# 3_iip_quad_uart.net
KiCad netlist of a schematic drawn in Altium Designer
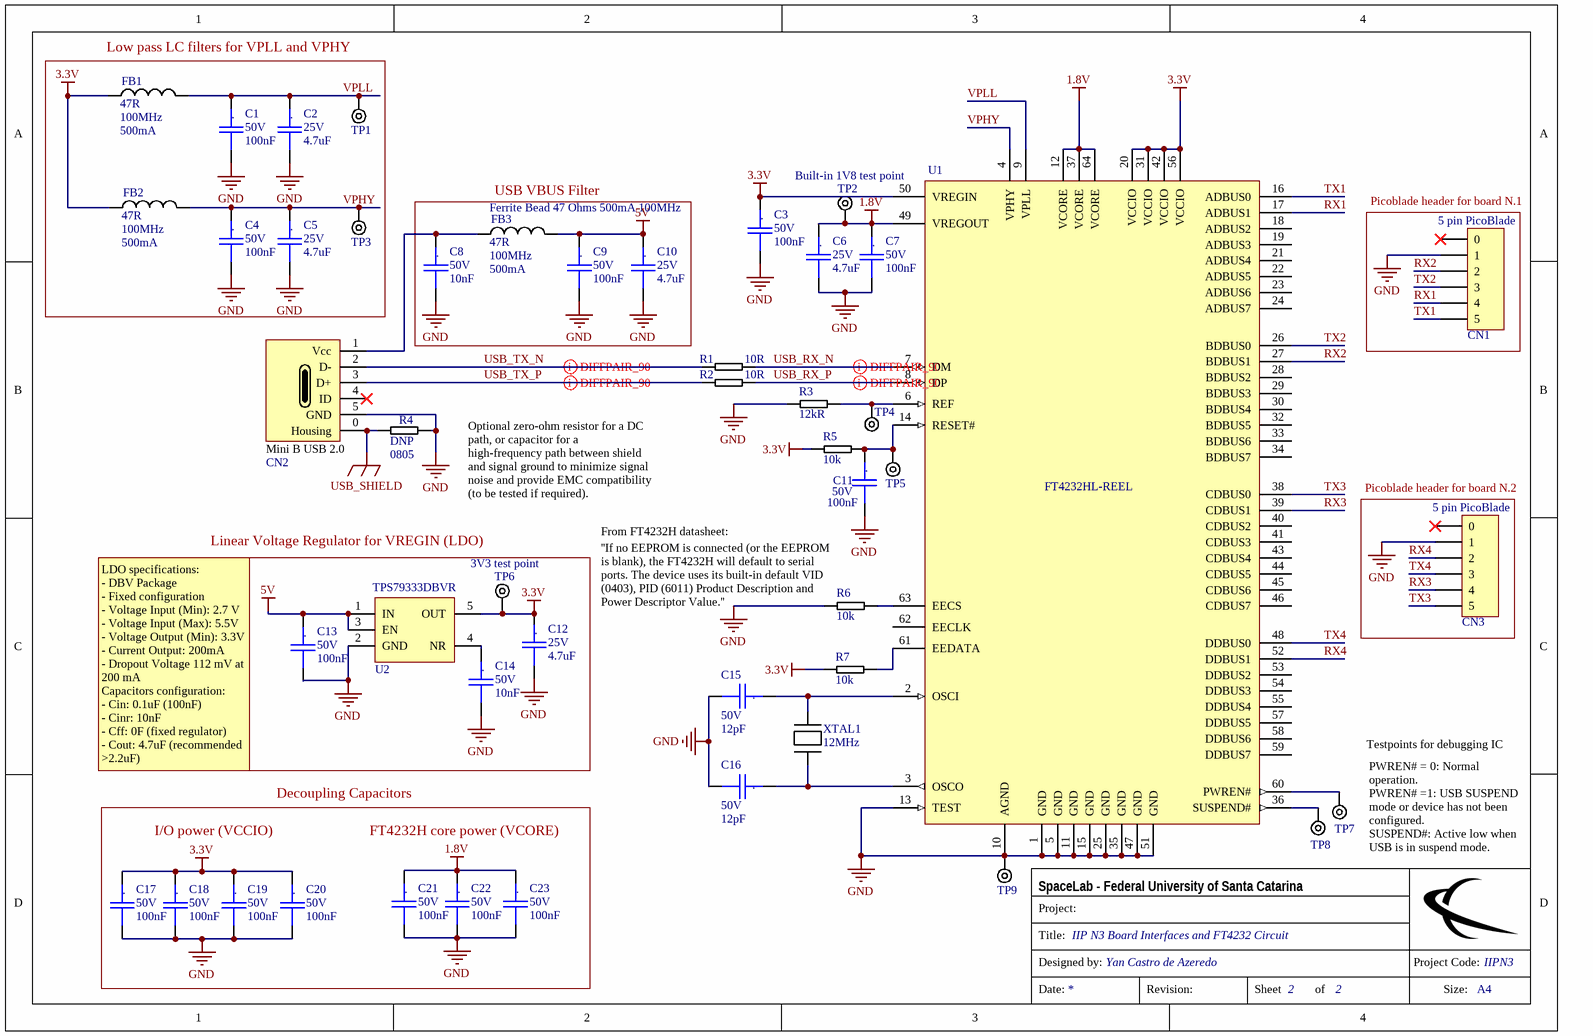
[diagram p0: 3_iip_quad_uart.SchDoc]

(export (version "E")
  (design (tool "Eeschema 10.0.6"))
  (components
    (comp (ref "C1")
      (value "0.1 uF, 0603 (1608 metric)")
      (footprint "C0603_MD")
      (fields
        (field (name "MANUFACTURER") "TDK")
        (field (name "TOLERANCE") "10%")
        (field (name "VOLTAGE") "50V")
        (field (name "VOLTAGE RATING") "50V")
        (field (name "CAPACITANCE") "100nF")
      )
      (libsource (lib "IB_floripasat2") (part "C1608X7R1H104K080AA"))
    )
    (comp (ref "C2")
      (value "4.7 uF, 0802 (2012 metric)")
      (footprint "C0805_MD")
      (description "Ceramic Capacitor SMD Multilayer, 0805 [2012 Metric], 4.7 uF, 25 V,  10%, X7R, C Series")
      (fields
        (field (name "MANUFACTURER") "TDK")
        (field (name "TOLERANCE") "10%")
        (field (name "VOLTAGE RATING") "25V")
        (field (name "CAPACITANCE") "4.7uF")
      )
      (libsource (lib "IB_floripasat2") (part "C2012X7R1E475K125AB"))
    )
    (comp (ref "C3")
      (value "0.1 uF, 0603 (1608 metric)")
      (footprint "C0603_MD")
      (fields
        (field (name "MANUFACTURER") "TDK")
        (field (name "TOLERANCE") "10%")
        (field (name "VOLTAGE") "50V")
        (field (name "VOLTAGE RATING") "50V")
        (field (name "CAPACITANCE") "100nF")
      )
      (libsource (lib "IB_floripasat2") (part "C1608X7R1H104K080AA"))
    )
    (comp (ref "C4")
      (value "0.1 uF, 0603 (1608 metric)")
      (footprint "C0603_MD")
      (fields
        (field (name "MANUFACTURER") "TDK")
        (field (name "TOLERANCE") "10%")
        (field (name "VOLTAGE") "50V")
        (field (name "VOLTAGE RATING") "50V")
        (field (name "CAPACITANCE") "100nF")
      )
      (libsource (lib "IB_floripasat2") (part "C1608X7R1H104K080AA"))
    )
    (comp (ref "C5")
      (value "4.7 uF, 0802 (2012 metric)")
      (footprint "C0805_MD")
      (description "Ceramic Capacitor SMD Multilayer, 0805 [2012 Metric], 4.7 uF, 25 V,  10%, X7R, C Series")
      (fields
        (field (name "MANUFACTURER") "TDK")
        (field (name "TOLERANCE") "10%")
        (field (name "VOLTAGE RATING") "25V")
        (field (name "CAPACITANCE") "4.7uF")
      )
      (libsource (lib "IB_floripasat2") (part "C2012X7R1E475K125AB"))
    )
    (comp (ref "C6")
      (value "4.7 uF, 0802 (2012 metric)")
      (footprint "C0805_MD")
      (description "Ceramic Capacitor SMD Multilayer, 0805 [2012 Metric], 4.7 uF, 25 V,  10%, X7R, C Series")
      (fields
        (field (name "MANUFACTURER") "TDK")
        (field (name "TOLERANCE") "10%")
        (field (name "VOLTAGE RATING") "25V")
        (field (name "CAPACITANCE") "4.7uF")
      )
      (libsource (lib "IB_floripasat2") (part "C2012X7R1E475K125AB"))
    )
    (comp (ref "C7")
      (value "0.1 uF, 0603 (1608 metric)")
      (footprint "C0603_MD")
      (fields
        (field (name "MANUFACTURER") "TDK")
        (field (name "TOLERANCE") "10%")
        (field (name "VOLTAGE") "50V")
        (field (name "VOLTAGE RATING") "50V")
        (field (name "CAPACITANCE") "100nF")
      )
      (libsource (lib "IB_floripasat2") (part "C1608X7R1H104K080AA"))
    )
    (comp (ref "C8")
      (value "10000 pF, 0805 (2012 metric)")
      (footprint "C0805_MD")
      (fields
        (field (name "MANUFACTURER") "Kyocera AVX")
        (field (name "TOLERANCE") "10%")
        (field (name "MANUFACTURER PART NUMBER") "08055C103KAT4A")
        (field (name "VOLTAGE") "50V")
        (field (name "CAPACITANCE") "10nF")
      )
      (libsource (lib "IB_floripasat2") (part "08055C103KAT4A"))
    )
    (comp (ref "C9")
      (value "0.1 uF, 0603 (1608 metric)")
      (footprint "C0603_MD")
      (fields
        (field (name "MANUFACTURER") "TDK")
        (field (name "TOLERANCE") "10%")
        (field (name "VOLTAGE") "50V")
        (field (name "VOLTAGE RATING") "50V")
        (field (name "CAPACITANCE") "100nF")
      )
      (libsource (lib "IB_floripasat2") (part "C1608X7R1H104K080AA"))
    )
    (comp (ref "C10")
      (value "4.7 uF, 0802 (2012 metric)")
      (footprint "C0805_MD")
      (description "Ceramic Capacitor SMD Multilayer, 0805 [2012 Metric], 4.7 uF, 25 V,  10%, X7R, C Series")
      (fields
        (field (name "MANUFACTURER") "TDK")
        (field (name "TOLERANCE") "10%")
        (field (name "VOLTAGE RATING") "25V")
        (field (name "CAPACITANCE") "4.7uF")
      )
      (libsource (lib "IB_floripasat2") (part "C2012X7R1E475K125AB"))
    )
    (comp (ref "C11")
      (value "0.1 uF, 0603 (1608 metric)")
      (footprint "C0603_MD")
      (fields
        (field (name "MANUFACTURER") "TDK")
        (field (name "TOLERANCE") "10%")
        (field (name "VOLTAGE") "50V")
        (field (name "VOLTAGE RATING") "50V")
        (field (name "CAPACITANCE") "100nF")
      )
      (libsource (lib "IB_floripasat2") (part "C1608X7R1H104K080AA"))
    )
    (comp (ref "C12")
      (value "4.7 uF, 0802 (2012 metric)")
      (footprint "C0805_MD")
      (description "Ceramic Capacitor SMD Multilayer, 0805 [2012 Metric], 4.7 uF, 25 V,  10%, X7R, C Series")
      (fields
        (field (name "MANUFACTURER") "TDK")
        (field (name "TOLERANCE") "10%")
        (field (name "VOLTAGE RATING") "25V")
        (field (name "CAPACITANCE") "4.7uF")
      )
      (libsource (lib "IB_floripasat2") (part "C2012X7R1E475K125AB"))
    )
    (comp (ref "C13")
      (value "0.1 uF, 0603 (1608 metric)")
      (footprint "C0603_MD")
      (fields
        (field (name "MANUFACTURER") "TDK")
        (field (name "TOLERANCE") "10%")
        (field (name "VOLTAGE") "50V")
        (field (name "VOLTAGE RATING") "50V")
        (field (name "CAPACITANCE") "100nF")
      )
      (libsource (lib "IB_floripasat2") (part "C1608X7R1H104K080AA"))
    )
    (comp (ref "C14")
      (value "10000 pF, 0805 (2012 metric)")
      (footprint "C0805_MD")
      (fields
        (field (name "MANUFACTURER") "Kyocera AVX")
        (field (name "TOLERANCE") "10%")
        (field (name "MANUFACTURER PART NUMBER") "08055C103KAT4A")
        (field (name "VOLTAGE") "50V")
        (field (name "CAPACITANCE") "10nF")
      )
      (libsource (lib "IB_floripasat2") (part "08055C103KAT4A"))
    )
    (comp (ref "C15")
      (value "12 pF, 0603 (1608 metric)")
      (footprint "C0603_MD")
      (description "Cap Ceramic 12pF 50VDC C0G 5% SMD 0603 Paper T/R")
      (fields
        (field (name "MANUFACTURER") "Samsung")
        (field (name "MANUFACTURER PART NUMBER") "CL10C120JB8NNNC")
        (field (name "VOLTAGE") "50V")
        (field (name "CAPACITANCE") "12pF")
      )
      (libsource (lib "IB_floripasat2") (part "CL10C120JB8NNNC"))
    )
    (comp (ref "C16")
      (value "12 pF, 0603 (1608 metric)")
      (footprint "C0603_MD")
      (description "Cap Ceramic 12pF 50VDC C0G 5% SMD 0603 Paper T/R")
      (fields
        (field (name "MANUFACTURER") "Samsung")
        (field (name "MANUFACTURER PART NUMBER") "CL10C120JB8NNNC")
        (field (name "VOLTAGE") "50V")
        (field (name "CAPACITANCE") "12pF")
      )
      (libsource (lib "IB_floripasat2") (part "CL10C120JB8NNNC"))
    )
    (comp (ref "C17")
      (value "0.1 uF, 0603 (1608 metric)")
      (footprint "C0603_MD")
      (fields
        (field (name "MANUFACTURER") "TDK")
        (field (name "TOLERANCE") "10%")
        (field (name "VOLTAGE") "50V")
        (field (name "VOLTAGE RATING") "50V")
        (field (name "CAPACITANCE") "100nF")
      )
      (libsource (lib "IB_floripasat2") (part "C1608X7R1H104K080AA"))
    )
    (comp (ref "C18")
      (value "0.1 uF, 0603 (1608 metric)")
      (footprint "C0603_MD")
      (fields
        (field (name "MANUFACTURER") "TDK")
        (field (name "TOLERANCE") "10%")
        (field (name "VOLTAGE") "50V")
        (field (name "VOLTAGE RATING") "50V")
        (field (name "CAPACITANCE") "100nF")
      )
      (libsource (lib "IB_floripasat2") (part "C1608X7R1H104K080AA"))
    )
    (comp (ref "C19")
      (value "0.1 uF, 0603 (1608 metric)")
      (footprint "C0603_MD")
      (fields
        (field (name "MANUFACTURER") "TDK")
        (field (name "TOLERANCE") "10%")
        (field (name "VOLTAGE") "50V")
        (field (name "VOLTAGE RATING") "50V")
        (field (name "CAPACITANCE") "100nF")
      )
      (libsource (lib "IB_floripasat2") (part "C1608X7R1H104K080AA"))
    )
    (comp (ref "C20")
      (value "0.1 uF, 0603 (1608 metric)")
      (footprint "C0603_MD")
      (fields
        (field (name "MANUFACTURER") "TDK")
        (field (name "TOLERANCE") "10%")
        (field (name "VOLTAGE") "50V")
        (field (name "VOLTAGE RATING") "50V")
        (field (name "CAPACITANCE") "100nF")
      )
      (libsource (lib "IB_floripasat2") (part "C1608X7R1H104K080AA"))
    )
    (comp (ref "C21")
      (value "0.1 uF, 0603 (1608 metric)")
      (footprint "C0603_MD")
      (fields
        (field (name "MANUFACTURER") "TDK")
        (field (name "TOLERANCE") "10%")
        (field (name "VOLTAGE") "50V")
        (field (name "VOLTAGE RATING") "50V")
        (field (name "CAPACITANCE") "100nF")
      )
      (libsource (lib "IB_floripasat2") (part "C1608X7R1H104K080AA"))
    )
    (comp (ref "C22")
      (value "0.1 uF, 0603 (1608 metric)")
      (footprint "C0603_MD")
      (fields
        (field (name "MANUFACTURER") "TDK")
        (field (name "TOLERANCE") "10%")
        (field (name "VOLTAGE") "50V")
        (field (name "VOLTAGE RATING") "50V")
        (field (name "CAPACITANCE") "100nF")
      )
      (libsource (lib "IB_floripasat2") (part "C1608X7R1H104K080AA"))
    )
    (comp (ref "C23")
      (value "0.1 uF, 0603 (1608 metric)")
      (footprint "C0603_MD")
      (fields
        (field (name "MANUFACTURER") "TDK")
        (field (name "TOLERANCE") "10%")
        (field (name "VOLTAGE") "50V")
        (field (name "VOLTAGE RATING") "50V")
        (field (name "CAPACITANCE") "100nF")
      )
      (libsource (lib "IB_floripasat2") (part "C1608X7R1H104K080AA"))
    )
    (comp (ref "CN1")
      (value "5 pin PicoBlade")
      (footprint "PICO BLADE 0533980571")
      (description "Wire-To-Board Connector, Vertical, PicoBlade 53398 Series, Surface Mount, Header, 5, 1.25 mm")
      (fields (field (name "MANUFACTURER") "Molex") (field (name "MANUFACTURER PART NUMBER") "53398-0571"))
      (libsource (lib "IB_floripasat2") (part "53398-0571"))
    )
    (comp (ref "CN2")
      (value "Vertical mini B USB 2.0 port")
      (footprint "MINI USB B 180GRAUS WE")
      (fields
        (field (name "MANUFACTURER") "Wurth Electronics")
        (field (name "MANUFACTURER PART NUMBER") "651005136421")
      )
      (libsource (lib "IB_floripasat2") (part "651005136421"))
    )
    (comp (ref "CN3")
      (value "5 pin PicoBlade")
      (footprint "PICO BLADE 0533980571")
      (description "Wire-To-Board Connector, Vertical, PicoBlade 53398 Series, Surface Mount, Header, 5, 1.25 mm")
      (fields (field (name "MANUFACTURER") "Molex") (field (name "MANUFACTURER PART NUMBER") "53398-0571"))
      (libsource (lib "IB_floripasat2") (part "53398-0571"))
    )
    (comp (ref "FB1")
      (value "Ferrite Bead 47 Ohms 500mA 100MHz")
      (footprint "L0603")
      (description "WURTH ELEKTRONIK   742792608   FERRITE BEAD, 0.1 OHM, 0.5A, 0603")
      (fields
        (field (name "MANUFACTURER") "Wurth Electronics")
        (field (name "TOLERANCE") "25%")
        (field (name "IMPEDANCE") "47R")
        (field (name "TEST FREQUENCY") "100MHz")
        (field (name "CURRENT RATING") "500mA")
      )
      (libsource (lib "IB_floripasat2") (part "742792608"))
    )
    (comp (ref "FB2")
      (value "Ferrite Bead 47 Ohms 500mA 100MHz")
      (footprint "L0603")
      (description "WURTH ELEKTRONIK   742792608   FERRITE BEAD, 0.1 OHM, 0.5A, 0603")
      (fields
        (field (name "MANUFACTURER") "Wurth Electronics")
        (field (name "TOLERANCE") "25%")
        (field (name "IMPEDANCE") "47R")
        (field (name "TEST FREQUENCY") "100MHz")
        (field (name "CURRENT RATING") "500mA")
      )
      (libsource (lib "IB_floripasat2") (part "742792608"))
    )
    (comp (ref "FB3")
      (value "Ferrite Bead 47 Ohms 500mA 100MHz")
      (footprint "L0603")
      (description "WURTH ELEKTRONIK   742792608   FERRITE BEAD, 0.1 OHM, 0.5A, 0603")
      (fields
        (field (name "MANUFACTURER") "Wurth Electronics")
        (field (name "TOLERANCE") "25%")
        (field (name "IMPEDANCE") "47R")
        (field (name "TEST FREQUENCY") "100MHz")
        (field (name "CURRENT RATING") "500mA")
      )
      (libsource (lib "IB_floripasat2") (part "742792608"))
    )
    (comp (ref "R1")
      (value "RES 10 ohms (0603)")
      (footprint "R0603_MD")
      (description "YAGEO (PHYCOMP) - RC0603FR-0710RL - RES, THICK FILM, 10R, 1%, 0.1W, 0603")
      (fields
        (field (name "MANUFACTURER") "Yageo")
        (field (name "TOLERANCE") "1%")
        (field (name "RESISTANCE") "10R")
      )
      (libsource (lib "IB_floripasat2") (part "RC0603FR-0710RL"))
    )
    (comp (ref "R2")
      (value "RES 10 ohms (0603)")
      (footprint "R0603_MD")
      (description "YAGEO (PHYCOMP) - RC0603FR-0710RL - RES, THICK FILM, 10R, 1%, 0.1W, 0603")
      (fields
        (field (name "MANUFACTURER") "Yageo")
        (field (name "TOLERANCE") "1%")
        (field (name "RESISTANCE") "10R")
      )
      (libsource (lib "IB_floripasat2") (part "RC0603FR-0710RL"))
    )
    (comp (ref "R3")
      (value "RES 12K ohms (0805)")
      (footprint "R0805_MD")
      (description "Resistor, SMT, 0805, 12K Ohm, +/-1%, +/-100ppm, Thk Film, T/R Marked")
      (fields
        (field (name "MANUFACTURER") "Stackpole Electronics")
        (field (name "MANUFACTURER PART NUMBER") "RMCF0805FT12K0")
        (field (name "RESISTANCE") "12kR")
      )
      (libsource (lib "IB_floripasat2") (part "RMCF0805FT12K0"))
    )
    (comp (ref "R4")
      (value "DNP")
      (footprint "R0805_MD")
      (fields
        (field (name "MANUFACTURER") "Vishay")
        (field (name "TOLERANCE") "1%")
        (field (name "MANUFACTURER PART NUMBER") "CRCW08050000Z0EA")
        (field (name "CASE/PACKAGE") "0805")
      )
      (libsource (lib "IB_floripasat2") (part "CRCW08050000Z0EA"))
    )
    (comp (ref "R5")
      (value "10k")
      (footprint "R0805_MD")
      (description "RES 10.0K OHM 1/8W 1% 0805 SMD")
      (fields (field (name "MANUFACTURER") "Vishay Dale") (field (name "TOLERANCE") "1%"))
      (libsource (lib "IB_floripasat2") (part "CRCW080510K0FKEA"))
    )
    (comp (ref "R6")
      (value "10k")
      (footprint "R0805_MD")
      (description "RES 10.0K OHM 1/8W 1% 0805 SMD")
      (fields (field (name "MANUFACTURER") "Vishay Dale") (field (name "TOLERANCE") "1%"))
      (libsource (lib "IB_floripasat2") (part "CRCW080510K0FKEA"))
    )
    (comp (ref "R7")
      (value "10k")
      (footprint "R0805_MD")
      (description "RES 10.0K OHM 1/8W 1% 0805 SMD")
      (fields (field (name "MANUFACTURER") "Vishay Dale") (field (name "TOLERANCE") "1%"))
      (libsource (lib "IB_floripasat2") (part "CRCW080510K0FKEA"))
    )
    (comp (ref "TP1")
      (value "DNP")
      (footprint "TEST POINT PTH")
      (description "TEST POINT PAD")
      (libsource (lib "IB_floripasat2") (part "Test Point PTH"))
    )
    (comp (ref "TP2")
      (value "DNP")
      (footprint "TEST POINT PTH")
      (description "TEST POINT PAD")
      (libsource (lib "IB_floripasat2") (part "Test Point PTH"))
    )
    (comp (ref "TP3")
      (value "DNP")
      (footprint "TEST POINT PTH")
      (description "TEST POINT PAD")
      (libsource (lib "IB_floripasat2") (part "Test Point PTH"))
    )
    (comp (ref "TP4")
      (value "DNP")
      (footprint "TEST POINT PTH")
      (description "TEST POINT PAD")
      (libsource (lib "IB_floripasat2") (part "Test Point PTH"))
    )
    (comp (ref "TP5")
      (value "DNP")
      (footprint "TEST POINT PTH")
      (description "TEST POINT PAD")
      (libsource (lib "IB_floripasat2") (part "Test Point PTH"))
    )
    (comp (ref "TP6")
      (value "DNP")
      (footprint "TEST POINT PTH")
      (description "TEST POINT PAD")
      (libsource (lib "IB_floripasat2") (part "Test Point PTH"))
    )
    (comp (ref "TP7")
      (value "DNP")
      (footprint "TEST POINT PTH")
      (description "TEST POINT PAD")
      (libsource (lib "IB_floripasat2") (part "Test Point PTH"))
    )
    (comp (ref "TP8")
      (value "DNP")
      (footprint "TEST POINT PTH")
      (description "TEST POINT PAD")
      (libsource (lib "IB_floripasat2") (part "Test Point PTH"))
    )
    (comp (ref "TP9")
      (value "DNP")
      (footprint "TEST POINT PTH")
      (description "TEST POINT PAD")
      (libsource (lib "IB_floripasat2") (part "Test Point PTH"))
    )
    (comp (ref "U1")
      (value "FT4232HL-REEL")
      (footprint "LQFP-64")
      (description "FTDI - FT4232HL-REEL - USB-UART/MPSSE, 4232, QUAD, 64LQFP")
      (fields (field (name "MANUFACTURER") "FTDI"))
      (libsource (lib "IB_floripasat2") (part "FT4232HL-REEL"))
    )
    (comp (ref "U2")
      (value "TPS79333DBVR")
      (footprint "SOT23-5")
      (description "TEXAS INSTRUMENTS - TPS79333DBVR - IC, V REG, LINEAR, 0.2A, SOT-23-5")
      (fields (field (name "MANUFACTURER") "Texas Instruments"))
      (libsource (lib "IB_floripasat2") (part "TPS79333DBVR"))
    )
    (comp (ref "XTAL1")
      (value "12.000MHz 12pF")
      (footprint "TXC 7A Series")
      (description "Crystals 12.000MHz 30ppm 12pF -40C to 85C")
      (fields
        (field (name "MANUFACTURER") "TXC")
        (field (name "TOLERANCE") "30ppm")
        (field (name "FREQUENCY") "12MHz")
      )
      (libsource (lib "IB_floripasat2") (part "AA-12.000MAGE-T"))
    )
  )
  (nets
    (net (code "1") (name "/RX1") (class "Default")
      (node (ref "CN1") (pin "4") (pinfunction "4_4") (pintype "passive"))
      (node (ref "U1") (pin "17") (pinfunction "ADBUS1_17") (pintype "passive"))
    )
    (net (code "2") (name "/RX2") (class "Default")
      (node (ref "CN1") (pin "2") (pinfunction "2_2") (pintype "passive"))
      (node (ref "U1") (pin "27") (pinfunction "BDBUS1_27") (pintype "passive"))
    )
    (net (code "3") (name "/RX3") (class "Default")
      (node (ref "CN3") (pin "4") (pinfunction "4_4") (pintype "passive"))
      (node (ref "U1") (pin "39") (pinfunction "CDBUS1_39") (pintype "passive"))
    )
    (net (code "4") (name "/RX4") (class "Default")
      (node (ref "CN3") (pin "2") (pinfunction "2_2") (pintype "passive"))
      (node (ref "U1") (pin "52") (pinfunction "DDBUS1_52") (pintype "passive"))
    )
    (net (code "5") (name "/TX1") (class "Default")
      (node (ref "CN1") (pin "5") (pinfunction "5_5") (pintype "passive"))
      (node (ref "U1") (pin "16") (pinfunction "ADBUS0_16") (pintype "passive"))
    )
    (net (code "6") (name "/TX2") (class "Default")
      (node (ref "CN1") (pin "3") (pinfunction "3_3") (pintype "passive"))
      (node (ref "U1") (pin "26") (pinfunction "BDBUS0_26") (pintype "passive"))
    )
    (net (code "7") (name "/TX3") (class "Default")
      (node (ref "CN3") (pin "5") (pinfunction "5_5") (pintype "passive"))
      (node (ref "U1") (pin "38") (pinfunction "CDBUS0_38") (pintype "passive"))
    )
    (net (code "8") (name "/TX4") (class "Default")
      (node (ref "CN3") (pin "3") (pinfunction "3_3") (pintype "passive"))
      (node (ref "U1") (pin "48") (pinfunction "DDBUS0_48") (pintype "passive"))
    )
    (net (code "9") (name "/USB_RX_N") (class "Default")
      (node (ref "R1") (pin "2") (pinfunction "2_2") (pintype "passive"))
      (node (ref "U1") (pin "7") (pinfunction "DM_7") (pintype "bidirectional"))
    )
    (net (code "10") (name "/USB_RX_P") (class "Default")
      (node (ref "R2") (pin "2") (pinfunction "2_2") (pintype "passive"))
      (node (ref "U1") (pin "8") (pinfunction "DP_8") (pintype "bidirectional"))
    )
    (net (code "11") (name "/USB_TX_N") (class "Default")
      (node (ref "CN2") (pin "2") (pinfunction "D-_2") (pintype "passive"))
      (node (ref "R1") (pin "1") (pinfunction "1_1") (pintype "passive"))
    )
    (net (code "12") (name "/USB_TX_P") (class "Default")
      (node (ref "CN2") (pin "3") (pinfunction "D+_3") (pintype "passive"))
      (node (ref "R2") (pin "1") (pinfunction "1_1") (pintype "passive"))
    )
    (net (code "13") (name "/VPHY") (class "Default")
      (node (ref "C4") (pin "1") (pinfunction "1_1") (pintype "passive"))
      (node (ref "C5") (pin "1") (pinfunction "1_1") (pintype "passive"))
      (node (ref "FB2") (pin "2") (pinfunction "2_2") (pintype "passive"))
      (node (ref "TP3") (pin "1") (pinfunction "1_1") (pintype "passive"))
      (node (ref "U1") (pin "4") (pinfunction "VPHY_4") (pintype "power_in"))
    )
    (net (code "14") (name "/VPLL") (class "Default")
      (node (ref "C1") (pin "1") (pinfunction "1_1") (pintype "passive"))
      (node (ref "C2") (pin "1") (pinfunction "1_1") (pintype "passive"))
      (node (ref "FB1") (pin "2") (pinfunction "2_2") (pintype "passive"))
      (node (ref "TP1") (pin "1") (pinfunction "1_1") (pintype "passive"))
      (node (ref "U1") (pin "9") (pinfunction "VPLL_9") (pintype "power_in"))
    )
    (net (code "15") (name "1.8V") (class "Default")
      (node (ref "C21") (pin "1") (pinfunction "1_1") (pintype "passive"))
      (node (ref "C22") (pin "1") (pinfunction "1_1") (pintype "passive"))
      (node (ref "C23") (pin "1") (pinfunction "1_1") (pintype "passive"))
      (node (ref "C6") (pin "1") (pinfunction "1_1") (pintype "passive"))
      (node (ref "C7") (pin "1") (pinfunction "1_1") (pintype "passive"))
      (node (ref "TP2") (pin "1") (pinfunction "1_1") (pintype "passive"))
      (node (ref "U1") (pin "12") (pinfunction "VCORE_12") (pintype "power_in"))
      (node (ref "U1") (pin "37") (pinfunction "VCORE_37") (pintype "power_in"))
      (node (ref "U1") (pin "49") (pinfunction "VREGOUT_49") (pintype "passive"))
      (node (ref "U1") (pin "64") (pinfunction "VCORE_64") (pintype "power_in"))
    )
    (net (code "16") (name "3.3V") (class "Default")
      (node (ref "C12") (pin "1") (pinfunction "1_1") (pintype "passive"))
      (node (ref "C17") (pin "1") (pinfunction "1_1") (pintype "passive"))
      (node (ref "C18") (pin "1") (pinfunction "1_1") (pintype "passive"))
      (node (ref "C19") (pin "1") (pinfunction "1_1") (pintype "passive"))
      (node (ref "C20") (pin "1") (pinfunction "1_1") (pintype "passive"))
      (node (ref "C3") (pin "1") (pinfunction "1_1") (pintype "passive"))
      (node (ref "FB1") (pin "1") (pinfunction "1_1") (pintype "passive"))
      (node (ref "FB2") (pin "1") (pinfunction "1_1") (pintype "passive"))
      (node (ref "R5") (pin "1") (pinfunction "1_1") (pintype "passive"))
      (node (ref "R7") (pin "1") (pinfunction "1_1") (pintype "passive"))
      (node (ref "TP6") (pin "1") (pinfunction "1_1") (pintype "passive"))
      (node (ref "U1") (pin "20") (pinfunction "VCCIO_20") (pintype "power_in"))
      (node (ref "U1") (pin "31") (pinfunction "VCCIO_31") (pintype "power_in"))
      (node (ref "U1") (pin "42") (pinfunction "VCCIO_42") (pintype "power_in"))
      (node (ref "U1") (pin "50") (pinfunction "VREGIN_50") (pintype "passive"))
      (node (ref "U1") (pin "56") (pinfunction "VCCIO_56") (pintype "power_in"))
      (node (ref "U2") (pin "5") (pinfunction "OUT_5") (pintype "passive"))
    )
    (net (code "17") (name "5V") (class "Default")
      (node (ref "C10") (pin "1") (pinfunction "1_1") (pintype "passive"))
      (node (ref "C13") (pin "1") (pinfunction "1_1") (pintype "passive"))
      (node (ref "C9") (pin "1") (pinfunction "1_1") (pintype "passive"))
      (node (ref "FB3") (pin "2") (pinfunction "2_2") (pintype "passive"))
      (node (ref "U2") (pin "1") (pinfunction "IN_1") (pintype "passive"))
      (node (ref "U2") (pin "3") (pinfunction "EN_3") (pintype "passive"))
    )
    (net (code "18") (name "GND") (class "Default")
      (node (ref "C1") (pin "2") (pinfunction "2_2") (pintype "passive"))
      (node (ref "C10") (pin "2") (pinfunction "2_2") (pintype "passive"))
      (node (ref "C11") (pin "2") (pinfunction "2_2") (pintype "passive"))
      (node (ref "C12") (pin "2") (pinfunction "2_2") (pintype "passive"))
      (node (ref "C13") (pin "2") (pinfunction "2_2") (pintype "passive"))
      (node (ref "C14") (pin "2") (pinfunction "2_2") (pintype "passive"))
      (node (ref "C15") (pin "2") (pinfunction "2_2") (pintype "passive"))
      (node (ref "C16") (pin "2") (pinfunction "2_2") (pintype "passive"))
      (node (ref "C17") (pin "2") (pinfunction "2_2") (pintype "passive"))
      (node (ref "C18") (pin "2") (pinfunction "2_2") (pintype "passive"))
      (node (ref "C19") (pin "2") (pinfunction "2_2") (pintype "passive"))
      (node (ref "C2") (pin "2") (pinfunction "2_2") (pintype "passive"))
      (node (ref "C20") (pin "2") (pinfunction "2_2") (pintype "passive"))
      (node (ref "C21") (pin "2") (pinfunction "2_2") (pintype "passive"))
      (node (ref "C22") (pin "2") (pinfunction "2_2") (pintype "passive"))
      (node (ref "C23") (pin "2") (pinfunction "2_2") (pintype "passive"))
      (node (ref "C3") (pin "2") (pinfunction "2_2") (pintype "passive"))
      (node (ref "C4") (pin "2") (pinfunction "2_2") (pintype "passive"))
      (node (ref "C5") (pin "2") (pinfunction "2_2") (pintype "passive"))
      (node (ref "C6") (pin "2") (pinfunction "2_2") (pintype "passive"))
      (node (ref "C7") (pin "2") (pinfunction "2_2") (pintype "passive"))
      (node (ref "C8") (pin "2") (pinfunction "2_2") (pintype "passive"))
      (node (ref "C9") (pin "2") (pinfunction "2_2") (pintype "passive"))
      (node (ref "CN1") (pin "1") (pinfunction "1_1") (pintype "passive"))
      (node (ref "CN2") (pin "5") (pinfunction "GND_5") (pintype "passive"))
      (node (ref "CN3") (pin "1") (pinfunction "1_1") (pintype "passive"))
      (node (ref "R3") (pin "1") (pinfunction "1_1") (pintype "passive"))
      (node (ref "R4") (pin "2") (pinfunction "2_2") (pintype "passive"))
      (node (ref "R6") (pin "1") (pinfunction "1_1") (pintype "passive"))
      (node (ref "TP9") (pin "1") (pinfunction "1_1") (pintype "passive"))
      (node (ref "U1") (pin "1") (pinfunction "GND_1") (pintype "passive"))
      (node (ref "U1") (pin "10") (pinfunction "AGND_10") (pintype "passive"))
      (node (ref "U1") (pin "11") (pinfunction "GND_11") (pintype "passive"))
      (node (ref "U1") (pin "13") (pinfunction "TEST_13") (pintype "input"))
      (node (ref "U1") (pin "15") (pinfunction "GND_15") (pintype "passive"))
      (node (ref "U1") (pin "25") (pinfunction "GND_25") (pintype "passive"))
      (node (ref "U1") (pin "35") (pinfunction "GND_35") (pintype "passive"))
      (node (ref "U1") (pin "47") (pinfunction "GND_47") (pintype "passive"))
      (node (ref "U1") (pin "5") (pinfunction "GND_5") (pintype "passive"))
      (node (ref "U1") (pin "51") (pinfunction "GND_51") (pintype "passive"))
      (node (ref "U2") (pin "2") (pinfunction "GND_2") (pintype "passive"))
    )
    (net (code "19") (name "Net-(CN2-Vcc)") (class "Default")
      (node (ref "C8") (pin "1") (pinfunction "1_1") (pintype "passive"))
      (node (ref "CN2") (pin "1") (pinfunction "Vcc_1") (pintype "passive"))
      (node (ref "FB3") (pin "1") (pinfunction "1_1") (pintype "passive"))
    )
    (net (code "20") (name "Net-(U1-EECS)") (class "Default")
      (node (ref "R6") (pin "2") (pinfunction "2_2") (pintype "passive"))
      (node (ref "U1") (pin "63") (pinfunction "EECS_63") (pintype "passive"))
    )
    (net (code "21") (name "Net-(U1-EEDATA)") (class "Default")
      (node (ref "R7") (pin "2") (pinfunction "2_2") (pintype "passive"))
      (node (ref "U1") (pin "61") (pinfunction "EEDATA_61") (pintype "passive"))
    )
    (net (code "22") (name "Net-(U1-OSCI)") (class "Default")
      (node (ref "C15") (pin "1") (pinfunction "1_1") (pintype "passive"))
      (node (ref "U1") (pin "2") (pinfunction "OSCI_2") (pintype "input"))
      (node (ref "XTAL1") (pin "1") (pinfunction "1_1") (pintype "passive"))
    )
    (net (code "23") (name "Net-(U1-OSCO)") (class "Default")
      (node (ref "C16") (pin "1") (pinfunction "1_1") (pintype "passive"))
      (node (ref "U1") (pin "3") (pinfunction "OSCO_3") (pintype "output"))
      (node (ref "XTAL1") (pin "2") (pinfunction "2_2") (pintype "passive"))
    )
    (net (code "24") (name "Net-(U1-PWREN#)") (class "Default")
      (node (ref "TP7") (pin "1") (pinfunction "1_1") (pintype "passive"))
      (node (ref "U1") (pin "60") (pinfunction "PWREN#_60") (pintype "output"))
    )
    (net (code "25") (name "Net-(U1-REF)") (class "Default")
      (node (ref "R3") (pin "2") (pinfunction "2_2") (pintype "passive"))
      (node (ref "TP4") (pin "1") (pinfunction "1_1") (pintype "passive"))
      (node (ref "U1") (pin "6") (pinfunction "REF_6") (pintype "input"))
    )
    (net (code "26") (name "Net-(U1-RESET#)") (class "Default")
      (node (ref "C11") (pin "1") (pinfunction "1_1") (pintype "passive"))
      (node (ref "R5") (pin "2") (pinfunction "2_2") (pintype "passive"))
      (node (ref "TP5") (pin "1") (pinfunction "1_1") (pintype "passive"))
      (node (ref "U1") (pin "14") (pinfunction "RESET#_14") (pintype "input"))
    )
    (net (code "27") (name "Net-(U1-SUSPEND#)") (class "Default")
      (node (ref "TP8") (pin "1") (pinfunction "1_1") (pintype "passive"))
      (node (ref "U1") (pin "36") (pinfunction "SUSPEND#_36") (pintype "output"))
    )
    (net (code "28") (name "Net-(U2-NR)") (class "Default")
      (node (ref "C14") (pin "1") (pinfunction "1_1") (pintype "passive"))
      (node (ref "U2") (pin "4") (pinfunction "NR_4") (pintype "passive"))
    )
    (net (code "29") (name "USB_SHIELD") (class "Default")
      (node (ref "CN2") (pin "0") (pinfunction "Housing_0") (pintype "passive"))
      (node (ref "R4") (pin "1") (pinfunction "1_1") (pintype "passive"))
    )
    (net (code "30") (name "unconnected-(CN1-Pad0)") (class "Default")
      (node (ref "CN1") (pin "0") (pinfunction "0_0") (pintype "passive+no_connect"))
    )
    (net (code "31") (name "unconnected-(CN2-ID-Pad4)") (class "Default")
      (node (ref "CN2") (pin "4") (pinfunction "ID_4") (pintype "passive+no_connect"))
    )
    (net (code "32") (name "unconnected-(CN3-Pad0)") (class "Default")
      (node (ref "CN3") (pin "0") (pinfunction "0_0") (pintype "passive+no_connect"))
    )
    (net (code "33") (name "unconnected-(U1-ADBUS2-Pad18)") (class "Default")
      (node (ref "U1") (pin "18") (pinfunction "ADBUS2_18") (pintype "passive"))
    )
    (net (code "34") (name "unconnected-(U1-ADBUS3-Pad19)") (class "Default")
      (node (ref "U1") (pin "19") (pinfunction "ADBUS3_19") (pintype "passive"))
    )
    (net (code "35") (name "unconnected-(U1-ADBUS4-Pad21)") (class "Default")
      (node (ref "U1") (pin "21") (pinfunction "ADBUS4_21") (pintype "passive"))
    )
    (net (code "36") (name "unconnected-(U1-ADBUS5-Pad22)") (class "Default")
      (node (ref "U1") (pin "22") (pinfunction "ADBUS5_22") (pintype "passive"))
    )
    (net (code "37") (name "unconnected-(U1-ADBUS6-Pad23)") (class "Default")
      (node (ref "U1") (pin "23") (pinfunction "ADBUS6_23") (pintype "passive"))
    )
    (net (code "38") (name "unconnected-(U1-ADBUS7-Pad24)") (class "Default")
      (node (ref "U1") (pin "24") (pinfunction "ADBUS7_24") (pintype "passive"))
    )
    (net (code "39") (name "unconnected-(U1-BDBUS2-Pad28)") (class "Default")
      (node (ref "U1") (pin "28") (pinfunction "BDBUS2_28") (pintype "passive"))
    )
    (net (code "40") (name "unconnected-(U1-BDBUS3-Pad29)") (class "Default")
      (node (ref "U1") (pin "29") (pinfunction "BDBUS3_29") (pintype "passive"))
    )
    (net (code "41") (name "unconnected-(U1-BDBUS4-Pad30)") (class "Default")
      (node (ref "U1") (pin "30") (pinfunction "BDBUS4_30") (pintype "passive"))
    )
    (net (code "42") (name "unconnected-(U1-BDBUS5-Pad32)") (class "Default")
      (node (ref "U1") (pin "32") (pinfunction "BDBUS5_32") (pintype "passive"))
    )
    (net (code "43") (name "unconnected-(U1-BDBUS6-Pad33)") (class "Default")
      (node (ref "U1") (pin "33") (pinfunction "BDBUS6_33") (pintype "passive"))
    )
    (net (code "44") (name "unconnected-(U1-BDBUS7-Pad34)") (class "Default")
      (node (ref "U1") (pin "34") (pinfunction "BDBUS7_34") (pintype "passive"))
    )
    (net (code "45") (name "unconnected-(U1-CDBUS2-Pad40)") (class "Default")
      (node (ref "U1") (pin "40") (pinfunction "CDBUS2_40") (pintype "passive"))
    )
    (net (code "46") (name "unconnected-(U1-CDBUS3-Pad41)") (class "Default")
      (node (ref "U1") (pin "41") (pinfunction "CDBUS3_41") (pintype "passive"))
    )
    (net (code "47") (name "unconnected-(U1-CDBUS4-Pad43)") (class "Default")
      (node (ref "U1") (pin "43") (pinfunction "CDBUS4_43") (pintype "passive"))
    )
    (net (code "48") (name "unconnected-(U1-CDBUS5-Pad44)") (class "Default")
      (node (ref "U1") (pin "44") (pinfunction "CDBUS5_44") (pintype "passive"))
    )
    (net (code "49") (name "unconnected-(U1-CDBUS6-Pad45)") (class "Default")
      (node (ref "U1") (pin "45") (pinfunction "CDBUS6_45") (pintype "passive"))
    )
    (net (code "50") (name "unconnected-(U1-CDBUS7-Pad46)") (class "Default")
      (node (ref "U1") (pin "46") (pinfunction "CDBUS7_46") (pintype "passive"))
    )
    (net (code "51") (name "unconnected-(U1-DDBUS2-Pad53)") (class "Default")
      (node (ref "U1") (pin "53") (pinfunction "DDBUS2_53") (pintype "passive"))
    )
    (net (code "52") (name "unconnected-(U1-DDBUS3-Pad54)") (class "Default")
      (node (ref "U1") (pin "54") (pinfunction "DDBUS3_54") (pintype "passive"))
    )
    (net (code "53") (name "unconnected-(U1-DDBUS4-Pad55)") (class "Default")
      (node (ref "U1") (pin "55") (pinfunction "DDBUS4_55") (pintype "passive"))
    )
    (net (code "54") (name "unconnected-(U1-DDBUS5-Pad57)") (class "Default")
      (node (ref "U1") (pin "57") (pinfunction "DDBUS5_57") (pintype "passive"))
    )
    (net (code "55") (name "unconnected-(U1-DDBUS6-Pad58)") (class "Default")
      (node (ref "U1") (pin "58") (pinfunction "DDBUS6_58") (pintype "passive"))
    )
    (net (code "56") (name "unconnected-(U1-DDBUS7-Pad59)") (class "Default")
      (node (ref "U1") (pin "59") (pinfunction "DDBUS7_59") (pintype "passive"))
    )
    (net (code "57") (name "unconnected-(U1-EECLK-Pad62)") (class "Default")
      (node (ref "U1") (pin "62") (pinfunction "EECLK_62") (pintype "passive"))
    )
  )
)
